# STM.net
KiCad netlist of a schematic drawn in Altium Designer
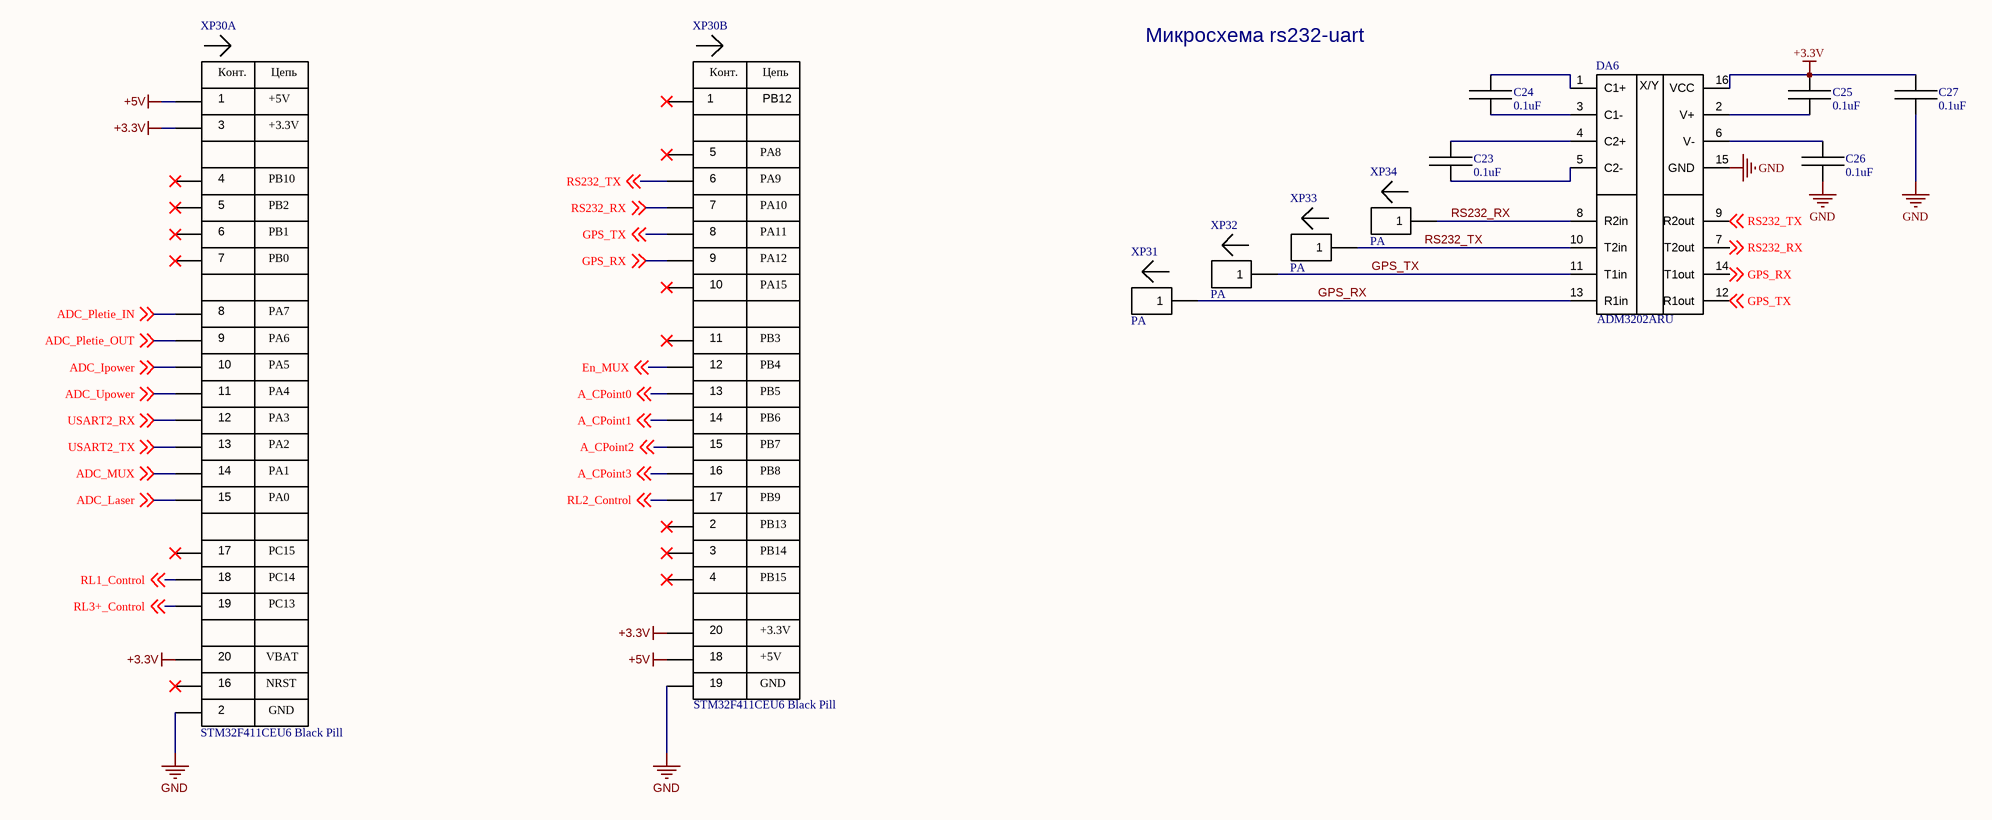
[diagram p0: STM.SchDoc]

(export (version "E")
  (design (tool "Eeschema 10.0.6"))
  (components
    (comp (ref "C23")
      (value "0.1uF")
      (footprint "0805C")
      (description "C0805 0.1UF 10% 50V")
      (fields
        (field (name "PART NUMBER") "SMD CAP CER 0.1UF ±10% 50V X7R 0805")
        (field (name "ADDED_BY") "anton@teslatec.ru")
      )
      (libsource (lib "Test_Stand_Pergam") (part "C0805-0.1UF 10% 50V"))
    )
    (comp (ref "C24")
      (value "0.1uF")
      (footprint "0805C")
      (description "C0805 0.1UF 10% 50V")
      (fields
        (field (name "PART NUMBER") "SMD CAP CER 0.1UF ±10% 50V X7R 0805")
        (field (name "ADDED_BY") "anton@teslatec.ru")
      )
      (libsource (lib "Test_Stand_Pergam") (part "C0805-0.1UF 10% 50V"))
    )
    (comp (ref "C25")
      (value "0.1uF")
      (footprint "0805C")
      (description "C0805 0.1UF 10% 50V")
      (fields
        (field (name "PART NUMBER") "SMD CAP CER 0.1UF ±10% 50V X7R 0805")
        (field (name "ADDED_BY") "anton@teslatec.ru")
      )
      (libsource (lib "Test_Stand_Pergam") (part "C0805-0.1UF 10% 50V"))
    )
    (comp (ref "C26")
      (value "0.1uF")
      (footprint "0805C")
      (description "C0805 0.1UF 10% 50V")
      (fields
        (field (name "PART NUMBER") "SMD CAP CER 0.1UF ±10% 50V X7R 0805")
        (field (name "ADDED_BY") "anton@teslatec.ru")
      )
      (libsource (lib "Test_Stand_Pergam") (part "C0805-0.1UF 10% 50V"))
    )
    (comp (ref "C27")
      (value "0.1uF")
      (footprint "0805C")
      (description "C0805 0.1UF 10% 50V")
      (fields
        (field (name "PART NUMBER") "SMD CAP CER 0.1UF ±10% 50V X7R 0805")
        (field (name "ADDED_BY") "anton@teslatec.ru")
      )
      (libsource (lib "Test_Stand_Pergam") (part "C0805-0.1UF 10% 50V"))
    )
    (comp (ref "DA6")
      (value "ADM3202ARU")
      (footprint "TSSOP-16")
      (description "Low Power, 3.3 V, RS-232\r\nLine Drivers/Receivers")
      (fields (field (name "ADDED_BY") "irdolgopolowa@yandex.ru"))
      (libsource (lib "Test_Stand_Pergam") (part "ADM3202ARU"))
    )
    (comp (ref "XP30")
      (value "STM32F411CEU6 Black Pill")
      (footprint "Black pill STM32F411CEU6")
      (description "STM32F411CEU6 Black pil")
      (fields
        (field (name "MATING PART") "2*DS1021-1*20SF11-B")
        (field (name "ADDED_BY") "irdolgopolowa@yandex.ru")
      )
      (libsource (lib "Test_Stand_Pergam") (part "STM32F411CEU6 Black pil"))
    )
    (comp (ref "XP31")
      (value "PA")
      (footprint "POGO PIN P100-A2/B1")
      (description "Pogo pin, 33.35x1.36")
      (fields
        (field (name "PART NUMBER") "P100-A2 / P100-A")
        (field (name "ADDED_BY") "irdolgopolowa@yandex.ru")
      )
      (libsource (lib "Test_Stand_Pergam") (part "P100-A2 / P100-A"))
    )
    (comp (ref "XP32")
      (value "PA")
      (footprint "POGO PIN P100-A2/B1")
      (description "Pogo pin, 33.35x1.36")
      (fields
        (field (name "PART NUMBER") "P100-A2 / P100-A")
        (field (name "ADDED_BY") "irdolgopolowa@yandex.ru")
      )
      (libsource (lib "Test_Stand_Pergam") (part "P100-A2 / P100-A"))
    )
    (comp (ref "XP33")
      (value "PA")
      (footprint "POGO PIN P100-A2/B1")
      (description "Pogo pin, 33.35x1.36")
      (fields
        (field (name "PART NUMBER") "P100-A2 / P100-A")
        (field (name "ADDED_BY") "irdolgopolowa@yandex.ru")
      )
      (libsource (lib "Test_Stand_Pergam") (part "P100-A2 / P100-A"))
    )
    (comp (ref "XP34")
      (value "PA")
      (footprint "POGO PIN P100-A2/B1")
      (description "Pogo pin, 33.35x1.36")
      (fields
        (field (name "PART NUMBER") "P100-A2 / P100-A")
        (field (name "ADDED_BY") "irdolgopolowa@yandex.ru")
      )
      (libsource (lib "Test_Stand_Pergam") (part "P100-A2 / P100-A"))
    )
  )
  (nets
    (net (code "1") (name "+3.3V") (class "Default")
      (node (ref "C25") (pin "2") (pinfunction "2_2") (pintype "passive"))
      (node (ref "C27") (pin "2") (pinfunction "2_2") (pintype "passive"))
      (node (ref "DA6") (pin "16") (pinfunction "VCC_16") (pintype "passive"))
      (node (ref "XP30") (pin "20") (pinfunction "VBAT_20") (pintype "passive"))
      (node (ref "XP30") (pin "3") (pinfunction "+3.3V_3") (pintype "passive"))
      (node (ref "XP30") (pin "40") (pinfunction "+3.3V_40") (pintype "passive"))
    )
    (net (code "2") (name "+5V") (class "Default")
      (node (ref "XP30") (pin "1") (pinfunction "+5V_1") (pintype "passive"))
      (node (ref "XP30") (pin "38") (pinfunction "+5V_38") (pintype "passive"))
    )
    (net (code "3") (name "ADC_Ipower") (class "Default")
      (node (ref "XP30") (pin "10") (pinfunction "PA5_10") (pintype "passive"))
    )
    (net (code "4") (name "ADC_Laser") (class "Default")
      (node (ref "XP30") (pin "15") (pinfunction "PA0_15") (pintype "passive"))
    )
    (net (code "5") (name "ADC_MUX") (class "Default")
      (node (ref "XP30") (pin "14") (pinfunction "PA1_14") (pintype "passive"))
    )
    (net (code "6") (name "ADC_Pletie_IN") (class "Default")
      (node (ref "XP30") (pin "8") (pinfunction "PA7_8") (pintype "passive"))
    )
    (net (code "7") (name "ADC_Pletie_OUT") (class "Default")
      (node (ref "XP30") (pin "9") (pinfunction "PA6_9") (pintype "passive"))
    )
    (net (code "8") (name "ADC_Upower") (class "Default")
      (node (ref "XP30") (pin "11") (pinfunction "PA4_11") (pintype "passive"))
    )
    (net (code "9") (name "A_CPoint0") (class "Default")
      (node (ref "XP30") (pin "33") (pinfunction "PB5_33") (pintype "passive"))
    )
    (net (code "10") (name "A_CPoint1") (class "Default")
      (node (ref "XP30") (pin "34") (pinfunction "PB6_34") (pintype "passive"))
    )
    (net (code "11") (name "A_CPoint2") (class "Default")
      (node (ref "XP30") (pin "35") (pinfunction "PB7_35") (pintype "passive"))
    )
    (net (code "12") (name "A_CPoint3") (class "Default")
      (node (ref "XP30") (pin "36") (pinfunction "PB8_36") (pintype "passive"))
    )
    (net (code "13") (name "En_MUX") (class "Default")
      (node (ref "XP30") (pin "32") (pinfunction "PB4_32") (pintype "passive"))
    )
    (net (code "14") (name "GND") (class "Default")
      (node (ref "C26") (pin "1") (pinfunction "1_1") (pintype "passive"))
      (node (ref "C27") (pin "1") (pinfunction "1_1") (pintype "passive"))
      (node (ref "DA6") (pin "15") (pinfunction "GND_15") (pintype "passive"))
      (node (ref "XP30") (pin "2") (pinfunction "GND_2") (pintype "passive"))
      (node (ref "XP30") (pin "39") (pinfunction "GND_39") (pintype "passive"))
    )
    (net (code "15") (name "GPS_RX") (class "Default")
      (node (ref "DA6") (pin "13") (pinfunction "R1in_13") (pintype "passive"))
      (node (ref "DA6") (pin "14") (pinfunction "T1out_14") (pintype "passive"))
      (node (ref "XP30") (pin "29") (pinfunction "PA12_29") (pintype "passive"))
      (node (ref "XP31") (pin "1") (pinfunction "1_1") (pintype "passive"))
    )
    (net (code "16") (name "GPS_TX") (class "Default")
      (node (ref "DA6") (pin "11") (pinfunction "T1in_11") (pintype "passive"))
      (node (ref "DA6") (pin "12") (pinfunction "R1out_12") (pintype "passive"))
      (node (ref "XP30") (pin "28") (pinfunction "PA11_28") (pintype "passive"))
      (node (ref "XP32") (pin "1") (pinfunction "1_1") (pintype "passive"))
    )
    (net (code "17") (name "Net-(DA6-C1+)") (class "Default")
      (node (ref "C24") (pin "2") (pinfunction "2_2") (pintype "passive"))
      (node (ref "DA6") (pin "1") (pinfunction "C1+_1") (pintype "passive"))
    )
    (net (code "18") (name "Net-(DA6-C1-)") (class "Default")
      (node (ref "C24") (pin "1") (pinfunction "1_1") (pintype "passive"))
      (node (ref "DA6") (pin "3") (pinfunction "C1-_3") (pintype "passive"))
    )
    (net (code "19") (name "Net-(DA6-C2+)") (class "Default")
      (node (ref "C23") (pin "2") (pinfunction "2_2") (pintype "passive"))
      (node (ref "DA6") (pin "4") (pinfunction "C2+_4") (pintype "passive"))
    )
    (net (code "20") (name "Net-(DA6-C2-)") (class "Default")
      (node (ref "C23") (pin "1") (pinfunction "1_1") (pintype "passive"))
      (node (ref "DA6") (pin "5") (pinfunction "C2-_5") (pintype "passive"))
    )
    (net (code "21") (name "Net-(DA6-V+)") (class "Default")
      (node (ref "C25") (pin "1") (pinfunction "1_1") (pintype "passive"))
      (node (ref "DA6") (pin "2") (pinfunction "V+_2") (pintype "passive"))
    )
    (net (code "22") (name "Net-(DA6-V-)") (class "Default")
      (node (ref "C26") (pin "2") (pinfunction "2_2") (pintype "passive"))
      (node (ref "DA6") (pin "6") (pinfunction "V-_6") (pintype "passive"))
    )
    (net (code "23") (name "RL1_Control") (class "Default")
      (node (ref "XP30") (pin "18") (pinfunction "PC14_18") (pintype "passive"))
    )
    (net (code "24") (name "RL2_Control") (class "Default")
      (node (ref "XP30") (pin "37") (pinfunction "PB9_37") (pintype "passive"))
    )
    (net (code "25") (name "RL3+_Control") (class "Default")
      (node (ref "XP30") (pin "19") (pinfunction "PC13_19") (pintype "passive"))
    )
    (net (code "26") (name "RS232_RX") (class "Default")
      (node (ref "DA6") (pin "7") (pinfunction "T2out_7") (pintype "passive"))
      (node (ref "DA6") (pin "8") (pinfunction "R2in_8") (pintype "passive"))
      (node (ref "XP30") (pin "27") (pinfunction "PA10_27") (pintype "passive"))
      (node (ref "XP34") (pin "1") (pinfunction "1_1") (pintype "passive"))
    )
    (net (code "27") (name "RS232_TX") (class "Default")
      (node (ref "DA6") (pin "10") (pinfunction "T2in_10") (pintype "passive"))
      (node (ref "DA6") (pin "9") (pinfunction "R2out_9") (pintype "passive"))
      (node (ref "XP30") (pin "26") (pinfunction "PA9_26") (pintype "passive"))
      (node (ref "XP33") (pin "1") (pinfunction "1_1") (pintype "passive"))
    )
    (net (code "28") (name "USART2_RX") (class "Default")
      (node (ref "XP30") (pin "12") (pinfunction "PA3_12") (pintype "passive"))
    )
    (net (code "29") (name "USART2_TX") (class "Default")
      (node (ref "XP30") (pin "13") (pinfunction "PA2_13") (pintype "passive"))
    )
    (net (code "30") (name "unconnected-(XP30A-NRST-Pad16)") (class "Default")
      (node (ref "XP30") (pin "16") (pinfunction "NRST_16") (pintype "passive+no_connect"))
    )
    (net (code "31") (name "unconnected-(XP30A-PB0-Pad7)") (class "Default")
      (node (ref "XP30") (pin "7") (pinfunction "PB0_7") (pintype "passive+no_connect"))
    )
    (net (code "32") (name "unconnected-(XP30A-PB1-Pad6)") (class "Default")
      (node (ref "XP30") (pin "6") (pinfunction "PB1_6") (pintype "passive+no_connect"))
    )
    (net (code "33") (name "unconnected-(XP30A-PB2-Pad5)") (class "Default")
      (node (ref "XP30") (pin "5") (pinfunction "PB2_5") (pintype "passive+no_connect"))
    )
    (net (code "34") (name "unconnected-(XP30A-PB10-Pad4)") (class "Default")
      (node (ref "XP30") (pin "4") (pinfunction "PB10_4") (pintype "passive+no_connect"))
    )
    (net (code "35") (name "unconnected-(XP30A-PC15-Pad17)") (class "Default")
      (node (ref "XP30") (pin "17") (pinfunction "PC15_17") (pintype "passive+no_connect"))
    )
    (net (code "36") (name "unconnected-(XP30B-PA8-Pad25)") (class "Default")
      (node (ref "XP30") (pin "25") (pinfunction "PA8_25") (pintype "passive+no_connect"))
    )
    (net (code "37") (name "unconnected-(XP30B-PA15-Pad30)") (class "Default")
      (node (ref "XP30") (pin "30") (pinfunction "PA15_30") (pintype "passive+no_connect"))
    )
    (net (code "38") (name "unconnected-(XP30B-PB3-Pad31)") (class "Default")
      (node (ref "XP30") (pin "31") (pinfunction "PB3_31") (pintype "passive+no_connect"))
    )
    (net (code "39") (name "unconnected-(XP30B-PB12-Pad21)") (class "Default")
      (node (ref "XP30") (pin "21") (pinfunction "PB12_21") (pintype "passive+no_connect"))
    )
    (net (code "40") (name "unconnected-(XP30B-PB13-Pad22)") (class "Default")
      (node (ref "XP30") (pin "22") (pinfunction "PB13_22") (pintype "passive+no_connect"))
    )
    (net (code "41") (name "unconnected-(XP30B-PB14-Pad23)") (class "Default")
      (node (ref "XP30") (pin "23") (pinfunction "PB14_23") (pintype "passive+no_connect"))
    )
    (net (code "42") (name "unconnected-(XP30B-PB15-Pad24)") (class "Default")
      (node (ref "XP30") (pin "24") (pinfunction "PB15_24") (pintype "passive+no_connect"))
    )
  )
)
